# electronic.net
KiCad netlist of a schematic drawn in Altium Designer
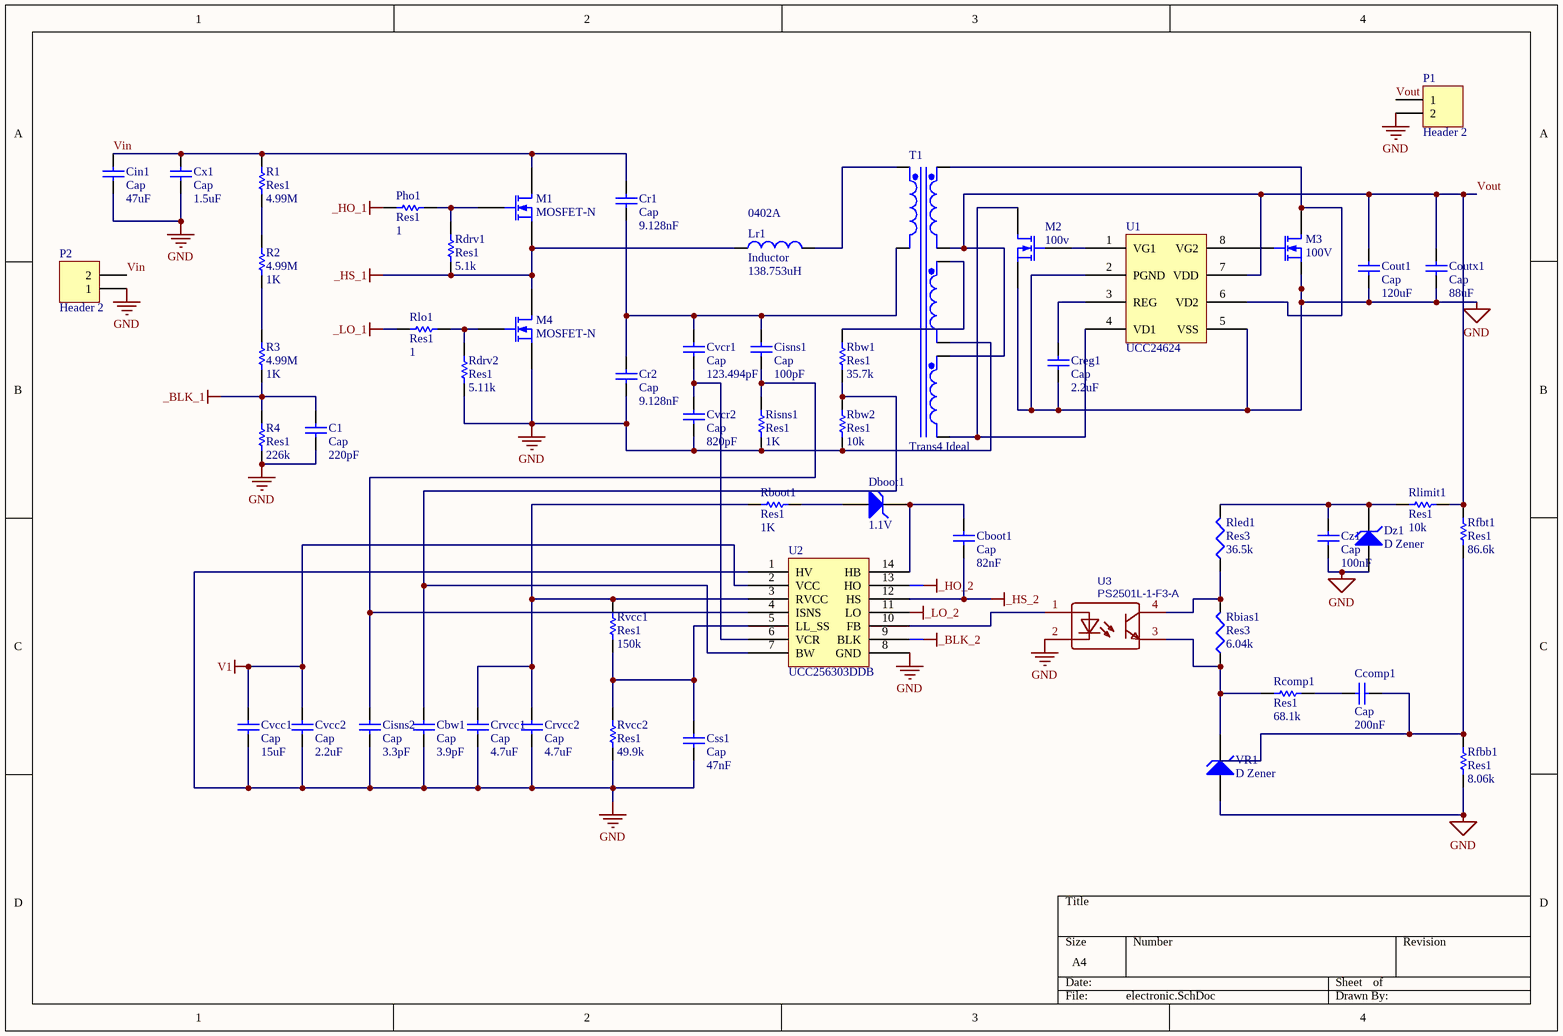
[diagram p0: electronic.SchDoc]

(export (version "E")
  (design (tool "Eeschema 10.0.6"))
  (components
    (comp (ref "C1")
      (value "Cap")
      (footprint "C0805")
      (description "Capacitor")
      (fields (field (name "ALTIUM_VALUE") "220pF") (field (name "PUBLISHER") "Altium Limited"))
      (libsource (lib "Miscellaneous Devices") (part "Cap"))
    )
    (comp (ref "Cboot1")
      (value "Cap")
      (footprint "C0805")
      (description "Capacitor")
      (fields (field (name "ALTIUM_VALUE") "82nF") (field (name "PUBLISHER") "Altium Limited"))
      (libsource (lib "Miscellaneous Devices") (part "Cap"))
    )
    (comp (ref "Cbw1")
      (value "Cap")
      (footprint "C0805")
      (description "Capacitor")
      (fields (field (name "ALTIUM_VALUE") "3.9pF") (field (name "PUBLISHER") "Altium Limited"))
      (libsource (lib "Miscellaneous Devices") (part "Cap"))
    )
    (comp (ref "Ccomp1")
      (value "Cap")
      (footprint "C0805")
      (description "Capacitor")
      (fields (field (name "ALTIUM_VALUE") "200nF") (field (name "PUBLISHER") "Altium Limited"))
      (libsource (lib "Miscellaneous Devices") (part "Cap"))
    )
    (comp (ref "Cin1")
      (value "Cap")
      (footprint "C0805")
      (description "Capacitor")
      (fields (field (name "ALTIUM_VALUE") "47uF") (field (name "PUBLISHER") "Altium Limited"))
      (libsource (lib "Miscellaneous Devices") (part "Cap"))
    )
    (comp (ref "Cisns1")
      (value "Cap")
      (footprint "C0805")
      (description "Capacitor")
      (fields (field (name "ALTIUM_VALUE") "100pF") (field (name "PUBLISHER") "Altium Limited"))
      (libsource (lib "Miscellaneous Devices") (part "Cap"))
    )
    (comp (ref "Cisns2")
      (value "Cap")
      (footprint "C0805")
      (description "Capacitor")
      (fields (field (name "ALTIUM_VALUE") "3.3pF") (field (name "PUBLISHER") "Altium Limited"))
      (libsource (lib "Miscellaneous Devices") (part "Cap"))
    )
    (comp (ref "Cout1")
      (value "Cap")
      (footprint "C0805")
      (description "Capacitor")
      (fields (field (name "ALTIUM_VALUE") "120uF") (field (name "PUBLISHER") "Altium Limited"))
      (libsource (lib "Miscellaneous Devices") (part "Cap"))
    )
    (comp (ref "Coutx1")
      (value "Cap")
      (footprint "C0805")
      (description "Capacitor")
      (fields (field (name "ALTIUM_VALUE") "88uF") (field (name "PUBLISHER") "Altium Limited"))
      (libsource (lib "Miscellaneous Devices") (part "Cap"))
    )
    (comp (ref "Cr1")
      (value "Cap")
      (footprint "C0805")
      (description "Capacitor")
      (fields (field (name "ALTIUM_VALUE") "9.128nF") (field (name "PUBLISHER") "Altium Limited"))
      (libsource (lib "Miscellaneous Devices") (part "Cap"))
    )
    (comp (ref "Cr2")
      (value "Cap")
      (footprint "C0805")
      (description "Capacitor")
      (fields (field (name "ALTIUM_VALUE") "9.128nF") (field (name "PUBLISHER") "Altium Limited"))
      (libsource (lib "Miscellaneous Devices") (part "Cap"))
    )
    (comp (ref "Creg1")
      (value "Cap")
      (footprint "C0805")
      (description "Capacitor")
      (fields (field (name "ALTIUM_VALUE") "2.2uF") (field (name "PUBLISHER") "Altium Limited"))
      (libsource (lib "Miscellaneous Devices") (part "Cap"))
    )
    (comp (ref "Crvcc1")
      (value "Cap")
      (footprint "C0805")
      (description "Capacitor")
      (fields (field (name "ALTIUM_VALUE") "4.7uF") (field (name "PUBLISHER") "Altium Limited"))
      (libsource (lib "Miscellaneous Devices") (part "Cap"))
    )
    (comp (ref "Crvcc2")
      (value "Cap")
      (footprint "C0805")
      (description "Capacitor")
      (fields (field (name "ALTIUM_VALUE") "4.7uF") (field (name "PUBLISHER") "Altium Limited"))
      (libsource (lib "Miscellaneous Devices") (part "Cap"))
    )
    (comp (ref "Css1")
      (value "Cap")
      (footprint "C0805")
      (description "Capacitor")
      (fields (field (name "ALTIUM_VALUE") "47nF") (field (name "PUBLISHER") "Altium Limited"))
      (libsource (lib "Miscellaneous Devices") (part "Cap"))
    )
    (comp (ref "Cvcc1")
      (value "Cap")
      (footprint "C0805")
      (description "Capacitor")
      (fields (field (name "ALTIUM_VALUE") "15uF") (field (name "PUBLISHER") "Altium Limited"))
      (libsource (lib "Miscellaneous Devices") (part "Cap"))
    )
    (comp (ref "Cvcc2")
      (value "Cap")
      (footprint "C0805")
      (description "Capacitor")
      (fields (field (name "ALTIUM_VALUE") "2.2uF") (field (name "PUBLISHER") "Altium Limited"))
      (libsource (lib "Miscellaneous Devices") (part "Cap"))
    )
    (comp (ref "Cvcr1")
      (value "Cap")
      (footprint "C0805")
      (description "Capacitor")
      (fields (field (name "ALTIUM_VALUE") "123.494pF") (field (name "PUBLISHER") "Altium Limited"))
      (libsource (lib "Miscellaneous Devices") (part "Cap"))
    )
    (comp (ref "Cvcr2")
      (value "Cap")
      (footprint "C0805")
      (description "Capacitor")
      (fields (field (name "ALTIUM_VALUE") "820pF") (field (name "PUBLISHER") "Altium Limited"))
      (libsource (lib "Miscellaneous Devices") (part "Cap"))
    )
    (comp (ref "Cx1")
      (value "Cap")
      (footprint "C0805")
      (description "Capacitor")
      (fields (field (name "ALTIUM_VALUE") "1.5uF") (field (name "PUBLISHER") "Altium Limited"))
      (libsource (lib "Miscellaneous Devices") (part "Cap"))
    )
    (comp (ref "Cz1")
      (value "Cap")
      (footprint "C0805")
      (description "Capacitor")
      (fields (field (name "ALTIUM_VALUE") "100nF") (field (name "PUBLISHER") "Altium Limited"))
      (libsource (lib "Miscellaneous Devices") (part "Cap"))
    )
    (comp (ref "Dboot1")
      (value "1.1V")
      (footprint "ST1300A - duplicate")
      (description "Zener Diode")
      (fields (field (name "PUBLISHER") "Altium Limited"))
      (libsource (lib "Miscellaneous Devices") (part "D Zener"))
    )
    (comp (ref "Dz1")
      (value "D Zener")
      (footprint "BZX84C11LT1G")
      (description "Zener Diode")
      (fields (field (name "PUBLISHER") "Altium Limited"))
      (libsource (lib "Miscellaneous Devices") (part "D Zener"))
    )
    (comp (ref "Lr1")
      (value "Inductor")
      (footprint "0402-A")
      (fields (field (name "ALTIUM_VALUE") "138.753uH") (field (name "PUBLISHER") "Altium Limited"))
      (libsource (lib "Miscellaneous Devices") (part "Inductor"))
    )
    (comp (ref "M1")
      (value "MOSFET-N")
      (footprint "FQDN30TM")
      (description "N-Channel MOSFET")
      (fields (field (name "PUBLISHER") "Altium Limited"))
      (libsource (lib "Miscellaneous Devices") (part "MOSFET-N"))
    )
    (comp (ref "M2")
      (value "100v")
      (footprint "CSD19538Q3A")
      (description "N-Channel MOSFET")
      (fields (field (name "PUBLISHER") "Altium Limited"))
      (libsource (lib "Miscellaneous Devices") (part "MOSFET-N"))
    )
    (comp (ref "M3")
      (value "100V")
      (footprint "CSD19538Q3A")
      (description "N-Channel MOSFET")
      (fields (field (name "PUBLISHER") "Altium Limited"))
      (libsource (lib "Miscellaneous Devices") (part "MOSFET-N"))
    )
    (comp (ref "M4")
      (value "MOSFET-N")
      (footprint "FQDN30TM")
      (description "N-Channel MOSFET")
      (fields (field (name "PUBLISHER") "Altium Limited"))
      (libsource (lib "Miscellaneous Devices") (part "MOSFET-N"))
    )
    (comp (ref "P1")
      (value "Header 2")
      (footprint "HDR1X2")
      (description "Header, 2-Pin")
      (fields (field (name "PUBLISHER") "Altium Limited"))
      (libsource (lib "") (part "Header 2_1"))
    )
    (comp (ref "P2")
      (value "Header 2")
      (footprint "HDR1X2")
      (description "Header, 2-Pin")
      (fields (field (name "PUBLISHER") "Altium Limited"))
      (libsource (lib "Miscellaneous Connectors") (part "Header 2"))
    )
    (comp (ref "Pho1")
      (value "Res1")
      (footprint "R 0805_M")
      (description "Resistor")
      (fields (field (name "ALTIUM_VALUE") "1") (field (name "PUBLISHER") "Altium Limited"))
      (libsource (lib "Miscellaneous Devices") (part "Res1"))
    )
    (comp (ref "R1")
      (value "Res1")
      (footprint "R 0805_M")
      (description "Resistor")
      (fields (field (name "ALTIUM_VALUE") "4.99M") (field (name "PUBLISHER") "Altium Limited"))
      (libsource (lib "Miscellaneous Devices") (part "Res1"))
    )
    (comp (ref "R2")
      (value "4.99M")
      (footprint "R 0805_M")
      (description "Resistor")
      (fields (field (name "ALTIUM_VALUE") "1K") (field (name "PUBLISHER") "Altium Limited"))
      (libsource (lib "Miscellaneous Devices") (part "Res1"))
    )
    (comp (ref "R3")
      (value "4.99M")
      (footprint "R 0805_M")
      (description "Resistor")
      (fields (field (name "ALTIUM_VALUE") "1K") (field (name "PUBLISHER") "Altium Limited"))
      (libsource (lib "Miscellaneous Devices") (part "Res1"))
    )
    (comp (ref "R4")
      (value "Res1")
      (footprint "R 0805_M")
      (description "Resistor")
      (fields (field (name "ALTIUM_VALUE") "226k") (field (name "PUBLISHER") "Altium Limited"))
      (libsource (lib "Miscellaneous Devices") (part "Res1"))
    )
    (comp (ref "Rbias1")
      (value "Res3")
      (footprint "R 0805_M")
      (description "Resistor")
      (fields (field (name "ALTIUM_VALUE") "6.04k") (field (name "PUBLISHER") "Altium Limited"))
      (libsource (lib "Miscellaneous Devices") (part "Res3"))
    )
    (comp (ref "Rboot1")
      (value "Res1")
      (footprint "R 0805_M")
      (description "Resistor")
      (fields (field (name "ALTIUM_VALUE") "1K") (field (name "PUBLISHER") "Altium Limited"))
      (libsource (lib "Miscellaneous Devices") (part "Res1"))
    )
    (comp (ref "Rbw1")
      (value "Res1")
      (footprint "R 0805_M")
      (description "Resistor")
      (fields (field (name "ALTIUM_VALUE") "35.7k") (field (name "PUBLISHER") "Altium Limited"))
      (libsource (lib "Miscellaneous Devices") (part "Res1"))
    )
    (comp (ref "Rbw2")
      (value "Res1")
      (footprint "R 0805_M")
      (description "Resistor")
      (fields (field (name "ALTIUM_VALUE") "10k") (field (name "PUBLISHER") "Altium Limited"))
      (libsource (lib "Miscellaneous Devices") (part "Res1"))
    )
    (comp (ref "Rcomp1")
      (value "Res1")
      (footprint "R 0805_M")
      (description "Resistor")
      (fields (field (name "ALTIUM_VALUE") "68.1k") (field (name "PUBLISHER") "Altium Limited"))
      (libsource (lib "Miscellaneous Devices") (part "Res1"))
    )
    (comp (ref "Rdrv1")
      (value "Res1")
      (footprint "R 0805_M")
      (description "Resistor")
      (fields (field (name "ALTIUM_VALUE") "5.1k") (field (name "PUBLISHER") "Altium Limited"))
      (libsource (lib "Miscellaneous Devices") (part "Res1"))
    )
    (comp (ref "Rdrv2")
      (value "Res1")
      (footprint "R 0805_M")
      (description "Resistor")
      (fields (field (name "ALTIUM_VALUE") "5.11k") (field (name "PUBLISHER") "Altium Limited"))
      (libsource (lib "Miscellaneous Devices") (part "Res1"))
    )
    (comp (ref "Rfbb1")
      (value "Res1")
      (footprint "R 0805_M")
      (description "Resistor")
      (fields (field (name "ALTIUM_VALUE") "8.06k") (field (name "PUBLISHER") "Altium Limited"))
      (libsource (lib "Miscellaneous Devices") (part "Res1"))
    )
    (comp (ref "Rfbt1")
      (value "Res1")
      (footprint "AXIAL-0.3")
      (description "Resistor")
      (fields (field (name "ALTIUM_VALUE") "86.6k") (field (name "PUBLISHER") "Altium Limited"))
      (libsource (lib "Miscellaneous Devices") (part "Res1"))
    )
    (comp (ref "Risns1")
      (value "Res1")
      (footprint "R 1206")
      (description "Resistor")
      (fields (field (name "ALTIUM_VALUE") "1K") (field (name "PUBLISHER") "Altium Limited"))
      (libsource (lib "Miscellaneous Devices") (part "Res1"))
    )
    (comp (ref "Rled1")
      (value "Res3")
      (footprint "R 0805_M")
      (description "Resistor")
      (fields (field (name "ALTIUM_VALUE") "36.5k") (field (name "PUBLISHER") "Altium Limited"))
      (libsource (lib "Miscellaneous Devices") (part "Res3"))
    )
    (comp (ref "Rlimit1")
      (value "Res1")
      (footprint "R 0805_M")
      (description "Resistor")
      (fields (field (name "ALTIUM_VALUE") "10k") (field (name "PUBLISHER") "Altium Limited"))
      (libsource (lib "Miscellaneous Devices") (part "Res1"))
    )
    (comp (ref "Rlo1")
      (value "Res1")
      (footprint "R 0805_M")
      (description "Resistor")
      (fields (field (name "ALTIUM_VALUE") "1") (field (name "PUBLISHER") "Altium Limited"))
      (libsource (lib "Miscellaneous Devices") (part "Res1"))
    )
    (comp (ref "Rvcc1")
      (value "Res1")
      (footprint "R 0805_M")
      (description "Resistor")
      (fields (field (name "ALTIUM_VALUE") "150k") (field (name "PUBLISHER") "Altium Limited"))
      (libsource (lib "Miscellaneous Devices") (part "Res1"))
    )
    (comp (ref "Rvcc2")
      (value "Res1")
      (footprint "R 0805_M")
      (description "Resistor")
      (fields (field (name "ALTIUM_VALUE") "49.9k") (field (name "PUBLISHER") "Altium Limited"))
      (libsource (lib "Miscellaneous Devices") (part "Res1"))
    )
    (comp (ref "T1")
      (value "Trans4 Ideal")
      (footprint "TRF_8")
      (description "Four-winding Transformer (Ideal)")
      (fields (field (name "PUBLISHER") "Altium Limited"))
      (libsource (lib "Miscellaneous Devices") (part "Trans4 Ideal"))
    )
    (comp (ref "U1")
      (value "UCC24624")
      (footprint "UCC24624")
      (libsource (lib "electronic") (part "UCC24624"))
    )
    (comp (ref "U2")
      (value "UCC256303DDB")
      (footprint "UCC256303")
      (libsource (lib "electronic") (part "UCC256303DDB"))
    )
    (comp (ref "U3")
      (value "PS2501L-1-F3-A")
      (footprint "PS2501-S")
      (fields (field (name "BOM_SUPPLIER PART") "C51825"))
      (libsource (lib "altium-import") (part "root_0_PS2501L-1-F3-A_"))
    )
    (comp (ref "VR1")
      (value "D Zener")
      (footprint "TLV431x")
      (description "Zener Diode")
      (fields (field (name "PUBLISHER") "Altium Limited"))
      (libsource (lib "Miscellaneous Devices") (part "D Zener"))
    )
  )
  (nets
    (net (code "1") (name "/Vin") (class "Default")
      (node (ref "Cin1") (pin "2") (pinfunction "2_2") (pintype "passive"))
      (node (ref "Cr1") (pin "2") (pinfunction "2_2") (pintype "passive"))
      (node (ref "Cx1") (pin "2") (pinfunction "2_2") (pintype "passive"))
      (node (ref "M1") (pin "1") (pinfunction "D_1") (pintype "passive"))
      (node (ref "P2") (pin "2") (pinfunction "2_2") (pintype "passive"))
      (node (ref "R1") (pin "2") (pinfunction "2_2") (pintype "passive"))
    )
    (net (code "2") (name "/Vout") (class "Default")
      (node (ref "Cout1") (pin "1") (pinfunction "1_1") (pintype "passive"))
      (node (ref "Coutx1") (pin "1") (pinfunction "1_1") (pintype "passive"))
      (node (ref "P1") (pin "1") (pinfunction "1_1") (pintype "passive"))
      (node (ref "Rfbt1") (pin "2") (pinfunction "2_2") (pintype "passive"))
      (node (ref "Rlimit1") (pin "2") (pinfunction "2_2") (pintype "passive"))
      (node (ref "T1") (pin "4") (pinfunction "Sec1-_4") (pintype "passive"))
      (node (ref "T1") (pin "7") (pinfunction "Sec3+_7") (pintype "passive"))
      (node (ref "U1") (pin "7") (pinfunction "VDD_7") (pintype "passive"))
    )
    (net (code "3") (name "GND") (class "Default")
      (node (ref "C1") (pin "1") (pinfunction "1_1") (pintype "passive"))
      (node (ref "Cbw1") (pin "1") (pinfunction "1_1") (pintype "passive"))
      (node (ref "Cin1") (pin "1") (pinfunction "1_1") (pintype "passive"))
      (node (ref "Cisns2") (pin "1") (pinfunction "1_1") (pintype "passive"))
      (node (ref "Cout1") (pin "2") (pinfunction "2_2") (pintype "passive"))
      (node (ref "Coutx1") (pin "2") (pinfunction "2_2") (pintype "passive"))
      (node (ref "Cr2") (pin "1") (pinfunction "1_1") (pintype "passive"))
      (node (ref "Creg1") (pin "1") (pinfunction "1_1") (pintype "passive"))
      (node (ref "Crvcc1") (pin "1") (pinfunction "1_1") (pintype "passive"))
      (node (ref "Crvcc2") (pin "1") (pinfunction "1_1") (pintype "passive"))
      (node (ref "Css1") (pin "2") (pinfunction "2_2") (pintype "passive"))
      (node (ref "Cvcc1") (pin "1") (pinfunction "1_1") (pintype "passive"))
      (node (ref "Cvcc2") (pin "1") (pinfunction "1_1") (pintype "passive"))
      (node (ref "Cvcr2") (pin "1") (pinfunction "1_1") (pintype "passive"))
      (node (ref "Cx1") (pin "1") (pinfunction "1_1") (pintype "passive"))
      (node (ref "Cz1") (pin "1") (pinfunction "1_1") (pintype "passive"))
      (node (ref "Dz1") (pin "1") (pinfunction "A_1") (pintype "passive"))
      (node (ref "M2") (pin "3") (pinfunction "S_3") (pintype "passive"))
      (node (ref "M3") (pin "3") (pinfunction "S_3") (pintype "passive"))
      (node (ref "M4") (pin "3") (pinfunction "S_3") (pintype "passive"))
      (node (ref "P1") (pin "2") (pinfunction "2_2") (pintype "passive"))
      (node (ref "P2") (pin "1") (pinfunction "1_1") (pintype "passive"))
      (node (ref "R4") (pin "1") (pinfunction "1_1") (pintype "passive"))
      (node (ref "Rbw2") (pin "1") (pinfunction "1_1") (pintype "passive"))
      (node (ref "Rdrv2") (pin "1") (pinfunction "1_1") (pintype "passive"))
      (node (ref "Rfbb1") (pin "1") (pinfunction "1_1") (pintype "passive"))
      (node (ref "Risns1") (pin "1") (pinfunction "1_1") (pintype "passive"))
      (node (ref "Rvcc2") (pin "1") (pinfunction "1_1") (pintype "passive"))
      (node (ref "T1") (pin "6") (pinfunction "Sec2-_6") (pintype "passive"))
      (node (ref "U1") (pin "2") (pinfunction "PGND_2") (pintype "passive"))
      (node (ref "U1") (pin "5") (pinfunction "VSS_5") (pintype "passive"))
      (node (ref "U2") (pin "1") (pinfunction "HV_1") (pintype "passive"))
      (node (ref "U2") (pin "8") (pinfunction "GND_8") (pintype "passive"))
      (node (ref "U3") (pin "2") (pinfunction "CAT_2") (pintype "passive"))
      (node (ref "VR1") (pin "1") (pinfunction "A_1") (pintype "passive"))
    )
    (net (code "4") (name "Net-(Ccomp1-Pad1)") (class "Default")
      (node (ref "Ccomp1") (pin "1") (pinfunction "1_1") (pintype "passive"))
      (node (ref "Rcomp1") (pin "2") (pinfunction "2_2") (pintype "passive"))
    )
    (net (code "5") (name "Net-(Ccomp1-Pad2)") (class "Default")
      (node (ref "Ccomp1") (pin "2") (pinfunction "2_2") (pintype "passive"))
      (node (ref "Rfbb1") (pin "2") (pinfunction "2_2") (pintype "passive"))
      (node (ref "Rfbt1") (pin "1") (pinfunction "1_1") (pintype "passive"))
    )
    (net (code "6") (name "Net-(Dboot1-A)") (class "Default")
      (node (ref "Dboot1") (pin "1") (pinfunction "A_1") (pintype "passive"))
      (node (ref "Rboot1") (pin "2") (pinfunction "2_2") (pintype "passive"))
    )
    (net (code "7") (name "Net-(Dboot1-K)") (class "Default")
      (node (ref "Cboot1") (pin "2") (pinfunction "2_2") (pintype "passive"))
      (node (ref "Dboot1") (pin "2") (pinfunction "K_2") (pintype "passive"))
      (node (ref "U2") (pin "14") (pinfunction "HB_14") (pintype "passive"))
    )
    (net (code "8") (name "Net-(Dz1-K)") (class "Default")
      (node (ref "Cz1") (pin "2") (pinfunction "2_2") (pintype "passive"))
      (node (ref "Dz1") (pin "2") (pinfunction "K_2") (pintype "passive"))
      (node (ref "Rled1") (pin "2") (pinfunction "2_2") (pintype "passive"))
      (node (ref "Rlimit1") (pin "1") (pinfunction "1_1") (pintype "passive"))
    )
    (net (code "9") (name "Net-(M1-G)") (class "Default")
      (node (ref "M1") (pin "2") (pinfunction "G_2") (pintype "passive"))
      (node (ref "Pho1") (pin "2") (pinfunction "2_2") (pintype "passive"))
      (node (ref "Rdrv1") (pin "2") (pinfunction "2_2") (pintype "passive"))
    )
    (net (code "10") (name "Net-(M2-D)") (class "Default")
      (node (ref "M2") (pin "1") (pinfunction "D_1") (pintype "passive"))
      (node (ref "T1") (pin "8") (pinfunction "Sec3-_8") (pintype "passive"))
      (node (ref "U1") (pin "4") (pinfunction "VD1_4") (pintype "passive"))
    )
    (net (code "11") (name "Net-(M2-G)") (class "Default")
      (node (ref "M2") (pin "2") (pinfunction "G_2") (pintype "passive"))
      (node (ref "U1") (pin "1") (pinfunction "VG1_1") (pintype "passive"))
    )
    (net (code "12") (name "Net-(M3-D)") (class "Default")
      (node (ref "M3") (pin "1") (pinfunction "D_1") (pintype "passive"))
      (node (ref "T1") (pin "3") (pinfunction "Sec1+_3") (pintype "passive"))
      (node (ref "U1") (pin "6") (pinfunction "VD2_6") (pintype "passive"))
    )
    (net (code "13") (name "Net-(M3-G)") (class "Default")
      (node (ref "M3") (pin "2") (pinfunction "G_2") (pintype "passive"))
      (node (ref "U1") (pin "8") (pinfunction "VG2_8") (pintype "passive"))
    )
    (net (code "14") (name "Net-(M4-G)") (class "Default")
      (node (ref "M4") (pin "2") (pinfunction "G_2") (pintype "passive"))
      (node (ref "Rdrv2") (pin "2") (pinfunction "2_2") (pintype "passive"))
      (node (ref "Rlo1") (pin "2") (pinfunction "2_2") (pintype "passive"))
    )
    (net (code "15") (name "Net-(R1-Pad1)") (class "Default")
      (node (ref "R1") (pin "1") (pinfunction "1_1") (pintype "passive"))
      (node (ref "R2") (pin "2") (pinfunction "2_2") (pintype "passive"))
    )
    (net (code "16") (name "Net-(R2-Pad1)") (class "Default")
      (node (ref "R2") (pin "1") (pinfunction "1_1") (pintype "passive"))
      (node (ref "R3") (pin "2") (pinfunction "2_2") (pintype "passive"))
    )
    (net (code "17") (name "Net-(T1-Pri+)") (class "Default")
      (node (ref "Lr1") (pin "2") (pinfunction "2_2") (pintype "passive"))
      (node (ref "T1") (pin "1") (pinfunction "Pri+_1") (pintype "passive"))
    )
    (net (code "18") (name "Net-(T1-Pri-)") (class "Default")
      (node (ref "Cisns1") (pin "2") (pinfunction "2_2") (pintype "passive"))
      (node (ref "Cr1") (pin "1") (pinfunction "1_1") (pintype "passive"))
      (node (ref "Cr2") (pin "2") (pinfunction "2_2") (pintype "passive"))
      (node (ref "Cvcr1") (pin "2") (pinfunction "2_2") (pintype "passive"))
      (node (ref "T1") (pin "2") (pinfunction "Pri-_2") (pintype "passive"))
    )
    (net (code "19") (name "Net-(T1-Sec2+)") (class "Default")
      (node (ref "Rbw1") (pin "2") (pinfunction "2_2") (pintype "passive"))
      (node (ref "T1") (pin "5") (pinfunction "Sec2+_5") (pintype "passive"))
    )
    (net (code "20") (name "Net-(U1-REG)") (class "Default")
      (node (ref "Creg1") (pin "2") (pinfunction "2_2") (pintype "passive"))
      (node (ref "U1") (pin "3") (pinfunction "REG_3") (pintype "passive"))
    )
    (net (code "21") (name "Net-(U2-BW)") (class "Default")
      (node (ref "Cbw1") (pin "2") (pinfunction "2_2") (pintype "passive"))
      (node (ref "Rbw1") (pin "1") (pinfunction "1_1") (pintype "passive"))
      (node (ref "Rbw2") (pin "2") (pinfunction "2_2") (pintype "passive"))
      (node (ref "U2") (pin "7") (pinfunction "BW_7") (pintype "passive"))
    )
    (net (code "22") (name "Net-(U2-FB)") (class "Default")
      (node (ref "U2") (pin "10") (pinfunction "FB_10") (pintype "passive"))
      (node (ref "U3") (pin "1") (pinfunction "AN_1") (pintype "passive"))
    )
    (net (code "23") (name "Net-(U2-ISNS)") (class "Default")
      (node (ref "Cisns1") (pin "1") (pinfunction "1_1") (pintype "passive"))
      (node (ref "Cisns2") (pin "2") (pinfunction "2_2") (pintype "passive"))
      (node (ref "Risns1") (pin "2") (pinfunction "2_2") (pintype "passive"))
      (node (ref "U2") (pin "4") (pinfunction "ISNS_4") (pintype "passive"))
    )
    (net (code "24") (name "Net-(U2-LL_SS)") (class "Default")
      (node (ref "Css1") (pin "1") (pinfunction "1_1") (pintype "passive"))
      (node (ref "Rvcc1") (pin "1") (pinfunction "1_1") (pintype "passive"))
      (node (ref "Rvcc2") (pin "2") (pinfunction "2_2") (pintype "passive"))
      (node (ref "U2") (pin "5") (pinfunction "LL_SS_5") (pintype "passive"))
    )
    (net (code "25") (name "Net-(U2-RVCC)") (class "Default")
      (node (ref "Crvcc1") (pin "2") (pinfunction "2_2") (pintype "passive"))
      (node (ref "Crvcc2") (pin "2") (pinfunction "2_2") (pintype "passive"))
      (node (ref "Rboot1") (pin "1") (pinfunction "1_1") (pintype "passive"))
      (node (ref "Rvcc1") (pin "2") (pinfunction "2_2") (pintype "passive"))
      (node (ref "U2") (pin "3") (pinfunction "RVCC_3") (pintype "passive"))
    )
    (net (code "26") (name "Net-(U2-VCR)") (class "Default")
      (node (ref "Cvcr1") (pin "1") (pinfunction "1_1") (pintype "passive"))
      (node (ref "Cvcr2") (pin "2") (pinfunction "2_2") (pintype "passive"))
      (node (ref "U2") (pin "6") (pinfunction "VCR_6") (pintype "passive"))
    )
    (net (code "27") (name "Net-(U3-COL)") (class "Default")
      (node (ref "Rbias1") (pin "2") (pinfunction "2_2") (pintype "passive"))
      (node (ref "Rled1") (pin "1") (pinfunction "1_1") (pintype "passive"))
      (node (ref "U3") (pin "4") (pinfunction "COL_4") (pintype "passive"))
    )
    (net (code "28") (name "Net-(U3-EM)") (class "Default")
      (node (ref "Rbias1") (pin "1") (pinfunction "1_1") (pintype "passive"))
      (node (ref "Rcomp1") (pin "1") (pinfunction "1_1") (pintype "passive"))
      (node (ref "U3") (pin "3") (pinfunction "EM_3") (pintype "passive"))
      (node (ref "VR1") (pin "2") (pinfunction "K_2") (pintype "passive"))
    )
    (net (code "29") (name "V1") (class "Default")
      (node (ref "Cvcc1") (pin "2") (pinfunction "2_2") (pintype "passive"))
      (node (ref "Cvcc2") (pin "2") (pinfunction "2_2") (pintype "passive"))
      (node (ref "U2") (pin "2") (pinfunction "VCC_2") (pintype "passive"))
    )
    (net (code "30") (name "_BLK_1") (class "Default")
      (node (ref "C1") (pin "2") (pinfunction "2_2") (pintype "passive"))
      (node (ref "R3") (pin "1") (pinfunction "1_1") (pintype "passive"))
      (node (ref "R4") (pin "2") (pinfunction "2_2") (pintype "passive"))
    )
    (net (code "31") (name "_BLK_2") (class "Default")
      (node (ref "U2") (pin "9") (pinfunction "BLK_9") (pintype "passive"))
    )
    (net (code "32") (name "_HO_1") (class "Default")
      (node (ref "Pho1") (pin "1") (pinfunction "1_1") (pintype "passive"))
    )
    (net (code "33") (name "_HO_2") (class "Default")
      (node (ref "U2") (pin "13") (pinfunction "HO_13") (pintype "passive"))
    )
    (net (code "34") (name "_HS_1") (class "Default")
      (node (ref "Lr1") (pin "1") (pinfunction "1_1") (pintype "passive"))
      (node (ref "M1") (pin "3") (pinfunction "S_3") (pintype "passive"))
      (node (ref "M4") (pin "1") (pinfunction "D_1") (pintype "passive"))
      (node (ref "Rdrv1") (pin "1") (pinfunction "1_1") (pintype "passive"))
    )
    (net (code "35") (name "_HS_2") (class "Default")
      (node (ref "Cboot1") (pin "1") (pinfunction "1_1") (pintype "passive"))
      (node (ref "U2") (pin "12") (pinfunction "HS_12") (pintype "passive"))
    )
    (net (code "36") (name "_LO_1") (class "Default")
      (node (ref "Rlo1") (pin "1") (pinfunction "1_1") (pintype "passive"))
    )
    (net (code "37") (name "_LO_2") (class "Default")
      (node (ref "U2") (pin "11") (pinfunction "LO_11") (pintype "passive"))
    )
  )
)
